# Shredmaster.net
KiCad netlist of a schematic drawn in Altium Designer
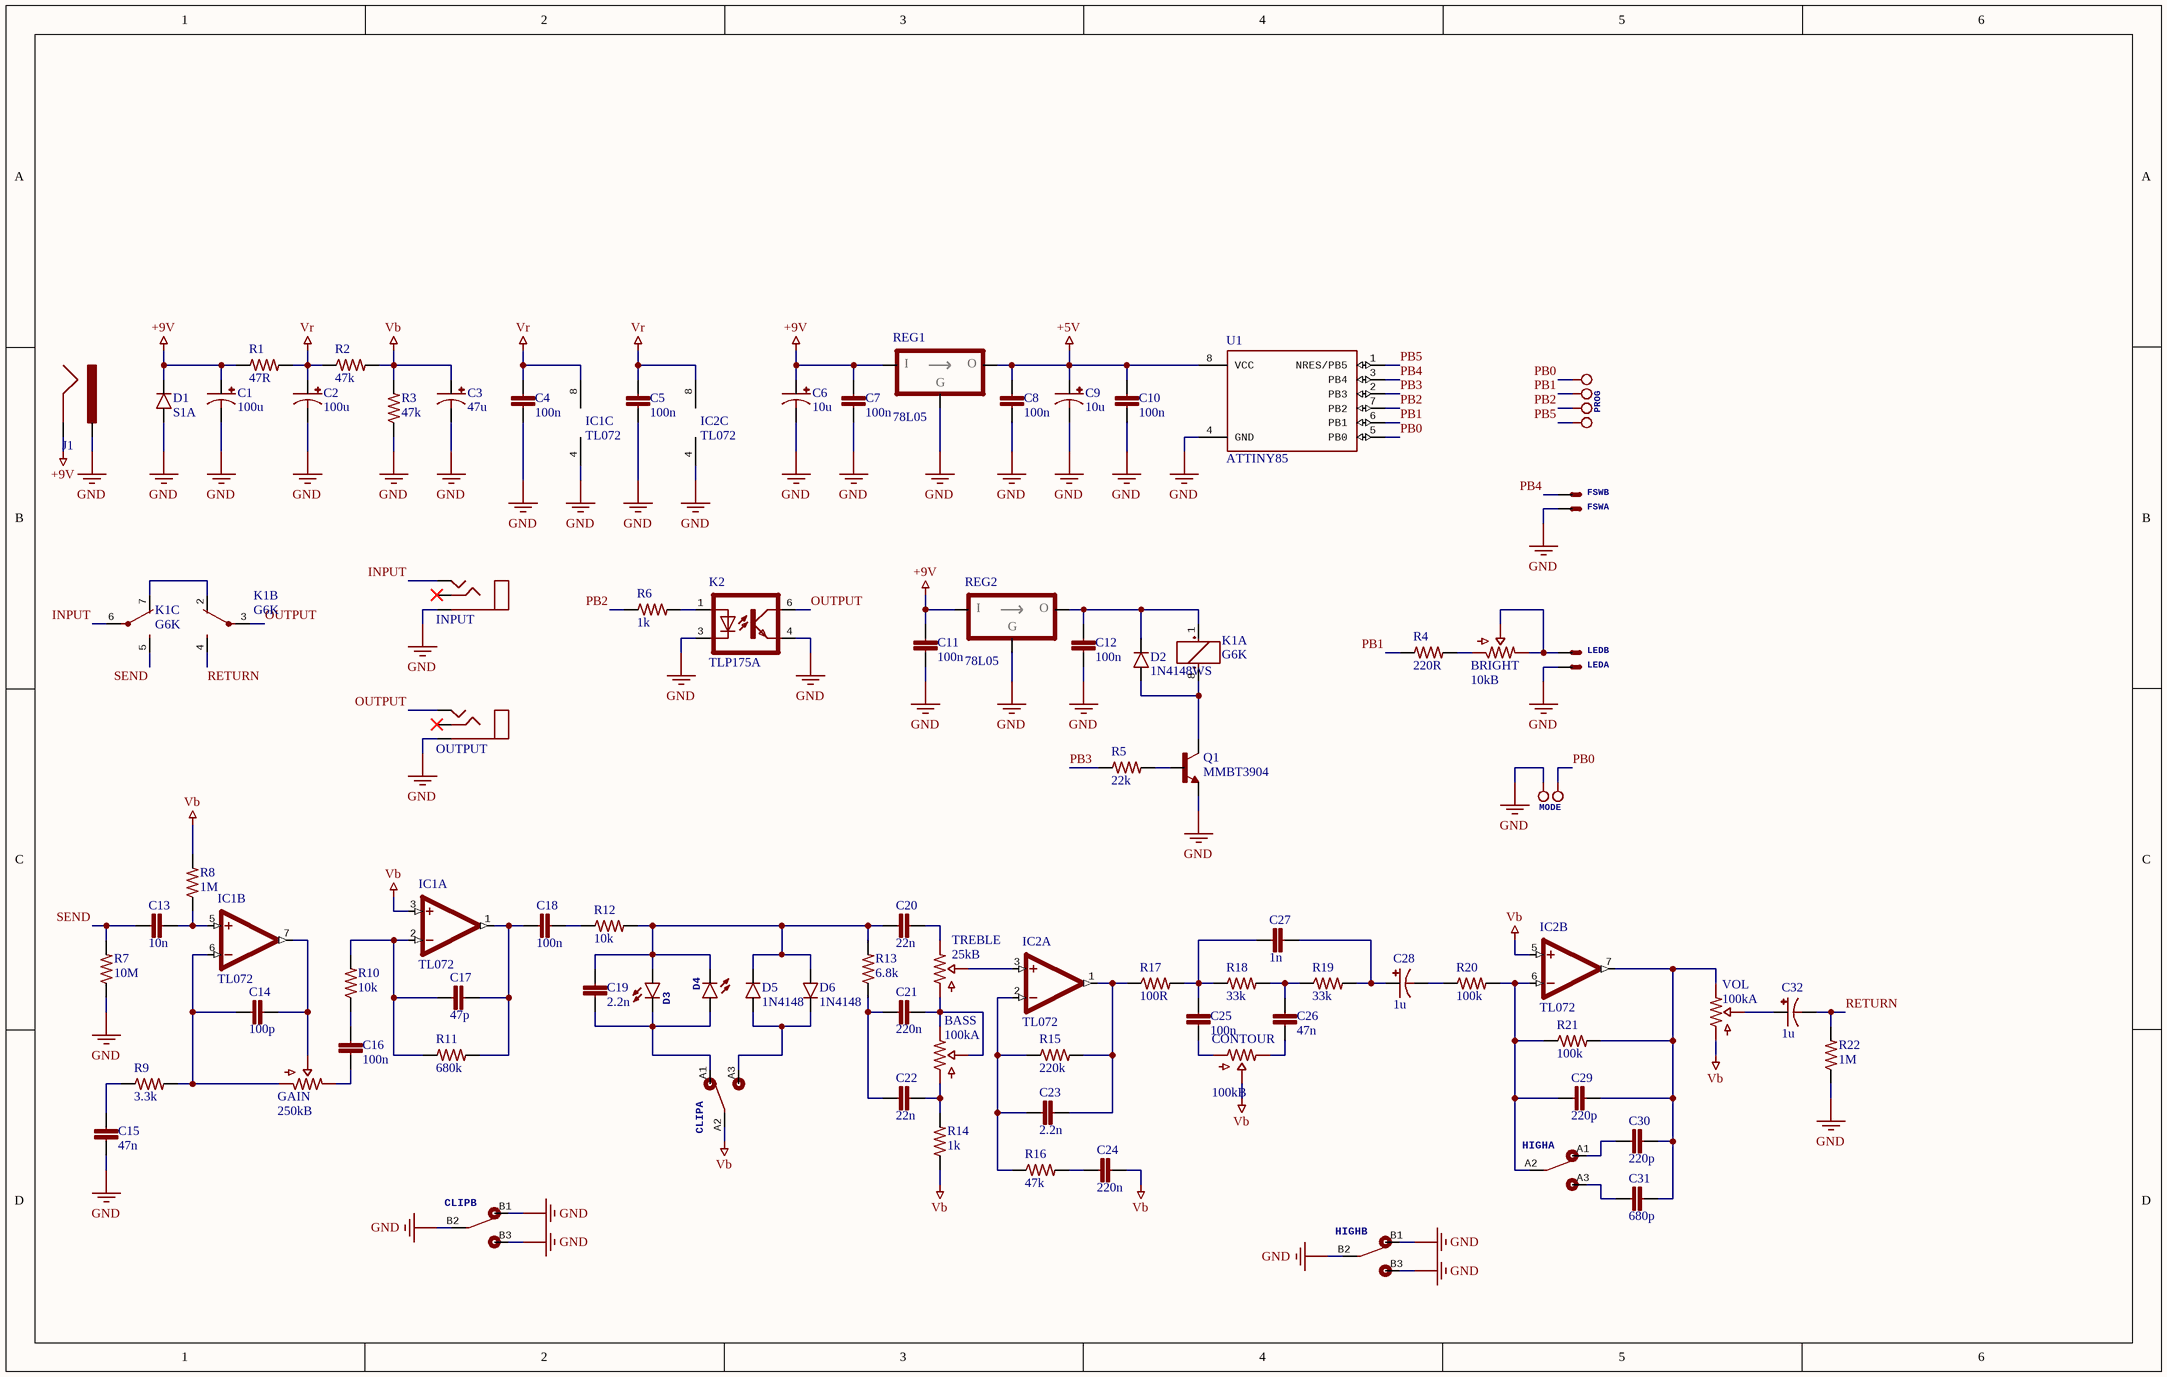
[diagram p0: Shredmaster.SchDoc]

(export (version "E")
  (design (tool "Eeschema 10.0.6"))
  (components
    (comp (ref "BASS")
      (value "100kA")
      (footprint "ALPHA_16mm_BOTTOM")
      (description "100k Log potentiometer round shaft")
      (libsource (lib "Pedals") (part "POT_100kA_ALPHA_16mm"))
    )
    (comp (ref "BRIGHT")
      (value "10kB")
      (footprint "BOURNS_3362P")
      (description "10k Lin 3362P trimmer")
      (libsource (lib "Pedals") (part "TRIM_10kB_3362P"))
    )
    (comp (ref "C1")
      (value "100u")
      (footprint "CAPAE_D")
      (description "CAP ALUM 100UF 25V SMD")
      (fields
        (field (name "MANUFACTURER") "Multicomp")
        (field (name "MANUFACTURER PART NUMBER") "MCVVT025M101EA6L")
      )
      (libsource (lib "Pedals SMD") (part "MCVVT025M101EA6L"))
    )
    (comp (ref "C2")
      (value "100u")
      (footprint "CAPAE_D")
      (description "CAP ALUM 100UF 25V SMD")
      (fields
        (field (name "MANUFACTURER") "Multicomp")
        (field (name "MANUFACTURER PART NUMBER") "MCVVT025M101EA6L")
      )
      (libsource (lib "Pedals SMD") (part "MCVVT025M101EA6L"))
    )
    (comp (ref "C3")
      (value "47u")
      (footprint "CAPAE_D")
      (description "CAP ALUM 47UF 25V SMD")
      (fields
        (field (name "MANUFACTURER") "Multicomp")
        (field (name "MANUFACTURER PART NUMBER") "MCVVT025M470EA1L")
      )
      (libsource (lib "Pedals SMD") (part "MCVVT025M470EA1L"))
    )
    (comp (ref "C4")
      (value "100n")
      (footprint "CHIP_0603")
      (description "CAP CER 100NF 50V X7R 0603")
      (fields
        (field (name "MANUFACTURER") "Multicomp")
        (field (name "MANUFACTURER PART NUMBER") "MC0603B104K500CT")
      )
      (libsource (lib "Pedals SMD") (part "MC0603B104K500CT"))
    )
    (comp (ref "C5")
      (value "100n")
      (footprint "CHIP_0603")
      (description "CAP CER 100NF 50V X7R 0603")
      (fields
        (field (name "MANUFACTURER") "Multicomp")
        (field (name "MANUFACTURER PART NUMBER") "MC0603B104K500CT")
      )
      (libsource (lib "Pedals SMD") (part "MC0603B104K500CT"))
    )
    (comp (ref "C6")
      (value "10u")
      (footprint "CAPAE_B")
      (description "CAP ALUM 10UF 25V SMD")
      (fields
        (field (name "MANUFACTURER") "Multicomp")
        (field (name "MANUFACTURER PART NUMBER") "MCVVT025M100CA1L")
      )
      (libsource (lib "Pedals SMD") (part "MCVVT025M100CA1L"))
    )
    (comp (ref "C7")
      (value "100n")
      (footprint "CHIP_0603")
      (description "CAP CER 100NF 50V X7R 0603")
      (fields
        (field (name "MANUFACTURER") "Multicomp")
        (field (name "MANUFACTURER PART NUMBER") "MC0603B104K500CT")
      )
      (libsource (lib "Pedals SMD") (part "MC0603B104K500CT"))
    )
    (comp (ref "C8")
      (value "100n")
      (footprint "CHIP_0603")
      (description "CAP CER 100NF 50V X7R 0603")
      (fields
        (field (name "MANUFACTURER") "Multicomp")
        (field (name "MANUFACTURER PART NUMBER") "MC0603B104K500CT")
      )
      (libsource (lib "Pedals SMD") (part "MC0603B104K500CT"))
    )
    (comp (ref "C9")
      (value "10u")
      (footprint "CAPAE_B")
      (description "CAP ALUM 10UF 25V SMD")
      (fields
        (field (name "MANUFACTURER") "Multicomp")
        (field (name "MANUFACTURER PART NUMBER") "MCVVT025M100CA1L")
      )
      (libsource (lib "Pedals SMD") (part "MCVVT025M100CA1L"))
    )
    (comp (ref "C10")
      (value "100n")
      (footprint "CHIP_0603")
      (description "CAP CER 100NF 50V X7R 0603")
      (fields
        (field (name "MANUFACTURER") "Multicomp")
        (field (name "MANUFACTURER PART NUMBER") "MC0603B104K500CT")
      )
      (libsource (lib "Pedals SMD") (part "MC0603B104K500CT"))
    )
    (comp (ref "C11")
      (value "100n")
      (footprint "CHIP_0603")
      (description "CAP CER 100NF 50V X7R 0603")
      (fields
        (field (name "MANUFACTURER") "Multicomp")
        (field (name "MANUFACTURER PART NUMBER") "MC0603B104K500CT")
      )
      (libsource (lib "Pedals SMD") (part "MC0603B104K500CT"))
    )
    (comp (ref "C12")
      (value "100n")
      (footprint "CHIP_0603")
      (description "CAP CER 100NF 50V X7R 0603")
      (fields
        (field (name "MANUFACTURER") "Multicomp")
        (field (name "MANUFACTURER PART NUMBER") "MC0603B104K500CT")
      )
      (libsource (lib "Pedals SMD") (part "MC0603B104K500CT"))
    )
    (comp (ref "C13")
      (value "10n")
      (footprint "CHIP_0603")
      (description "CAP CER 10NF 50V C0G/NP0 0603")
      (fields
        (field (name "MANUFACTURER") "Murata")
        (field (name "MANUFACTURER PART NUMBER") "GRM1885C1H103JA01D")
      )
      (libsource (lib "Pedals SMD") (part "GRM1885C1H103JA01D"))
    )
    (comp (ref "C14")
      (value "100p")
      (footprint "CHIP_0603")
      (description "CAP CER 100PF 50V C0G/NP0 0603")
      (fields
        (field (name "MANUFACTURER") "Multicomp")
        (field (name "MANUFACTURER PART NUMBER") "MC0603N101J500CT")
      )
      (libsource (lib "Pedals SMD") (part "MC0603N101J500CT"))
    )
    (comp (ref "C15")
      (value "47n")
      (footprint "CHIP_1206")
      (description "CAP CER 47NF 50V C0G/NP0 1206")
      (fields
        (field (name "MANUFACTURER") "Murata")
        (field (name "MANUFACTURER PART NUMBER") "GCM31M5C1H473JA16L")
      )
      (libsource (lib "Pedals SMD") (part "GCM31M5C1H473JA16L"))
    )
    (comp (ref "C16")
      (value "100n")
      (footprint "CHIP_1206")
      (description "CAP CER 100NF 50V C0G/NP0 1206")
      (fields
        (field (name "MANUFACTURER") "Murata")
        (field (name "MANUFACTURER PART NUMBER") "GRM31C5C1H104JA01L")
      )
      (libsource (lib "") (part "GRM31C5C1H104JA01L_1"))
    )
    (comp (ref "C17")
      (value "47p")
      (footprint "CHIP_0603")
      (description "CAP CER 47PF 50V C0G/NP0 0603")
      (fields
        (field (name "MANUFACTURER") "Multicomp")
        (field (name "MANUFACTURER PART NUMBER") "MC0603N470J500CT")
      )
      (libsource (lib "Pedals SMD") (part "MC0603N470J500CT"))
    )
    (comp (ref "C18")
      (value "100n")
      (footprint "CHIP_1206")
      (description "CAP CER 100NF 50V C0G/NP0 1206")
      (fields
        (field (name "MANUFACTURER") "Murata")
        (field (name "MANUFACTURER PART NUMBER") "GRM31C5C1H104JA01L")
      )
      (libsource (lib "Pedals SMD") (part "GRM31C5C1H104JA01L"))
    )
    (comp (ref "C19")
      (value "2.2n")
      (footprint "CHIP_0603")
      (description "CAP CER 2.2NF 50V C0G/NP0 0603")
      (fields
        (field (name "MANUFACTURER") "Murata")
        (field (name "MANUFACTURER PART NUMBER") "GRM1885C1H222JA01D")
      )
      (libsource (lib "") (part "GRM1885C1H222JA01D_1"))
    )
    (comp (ref "C20")
      (value "22n")
      (footprint "CHIP_0805")
      (description "CAP CER 22NF 50V C0G/NP0 0805")
      (fields
        (field (name "MANUFACTURER") "Murata")
        (field (name "MANUFACTURER PART NUMBER") "GRM21B5C1H223JA01L")
      )
      (libsource (lib "Pedals SMD") (part "GRM21B5C1H223JA01L"))
    )
    (comp (ref "C21")
      (value "220n")
      (footprint "CHIP_0603")
      (description "CAP CER 220n 50V X7R 0603")
      (fields
        (field (name "MANUFACTURER") "Murata")
        (field (name "MANUFACTURER PART NUMBER") "GCM188R71H224KA64D")
      )
      (libsource (lib "Pedals SMD") (part "GCM188R71H224KA64D"))
    )
    (comp (ref "C22")
      (value "22n")
      (footprint "CHIP_0805")
      (description "CAP CER 22NF 50V C0G/NP0 0805")
      (fields
        (field (name "MANUFACTURER") "Murata")
        (field (name "MANUFACTURER PART NUMBER") "GRM21B5C1H223JA01L")
      )
      (libsource (lib "Pedals SMD") (part "GRM21B5C1H223JA01L"))
    )
    (comp (ref "C23")
      (value "2.2n")
      (footprint "CHIP_0603")
      (description "CAP CER 2.2NF 50V C0G/NP0 0603")
      (fields
        (field (name "MANUFACTURER") "Murata")
        (field (name "MANUFACTURER PART NUMBER") "GRM1885C1H222JA01D")
      )
      (libsource (lib "Pedals SMD") (part "GRM1885C1H222JA01D"))
    )
    (comp (ref "C24")
      (value "220n")
      (footprint "CHIP_0603")
      (description "CAP CER 220n 50V X7R 0603")
      (fields
        (field (name "MANUFACTURER") "Murata")
        (field (name "MANUFACTURER PART NUMBER") "GCM188R71H224KA64D")
      )
      (libsource (lib "Pedals SMD") (part "GCM188R71H224KA64D"))
    )
    (comp (ref "C25")
      (value "100n")
      (footprint "CHIP_1206")
      (description "CAP CER 100NF 50V C0G/NP0 1206")
      (fields
        (field (name "MANUFACTURER") "Murata")
        (field (name "MANUFACTURER PART NUMBER") "GRM31C5C1H104JA01L")
      )
      (libsource (lib "") (part "GRM31C5C1H104JA01L_1"))
    )
    (comp (ref "C26")
      (value "47n")
      (footprint "CHIP_1206")
      (description "CAP CER 47NF 50V C0G/NP0 1206")
      (fields
        (field (name "MANUFACTURER") "Murata")
        (field (name "MANUFACTURER PART NUMBER") "GCM31M5C1H473JA16L")
      )
      (libsource (lib "Pedals SMD") (part "GCM31M5C1H473JA16L"))
    )
    (comp (ref "C27")
      (value "1n")
      (footprint "CHIP_0603")
      (description "CAP CER 1NF 50V C0G/NP0 0603")
      (fields
        (field (name "MANUFACTURER") "Murata")
        (field (name "MANUFACTURER PART NUMBER") "GRM1885C1H102JA01D")
      )
      (libsource (lib "Pedals SMD") (part "GRM1885C1H102JA01D"))
    )
    (comp (ref "C28")
      (value "1u")
      (footprint "CAPAE_B")
      (description "CAP ALUM 1UF 50V LESR SMD")
      (fields
        (field (name "MANUFACTURER") "Panasonic")
        (field (name "MANUFACTURER PART NUMBER") "EEEFC1H1R0R")
      )
      (libsource (lib "Pedals SMD") (part "EEEFC1H1R0R"))
    )
    (comp (ref "C29")
      (value "220p")
      (footprint "CHIP_0603")
      (description "CAP CER 220PF 50V C0G/NP0 0603")
      (fields
        (field (name "MANUFACTURER") "Multicomp")
        (field (name "MANUFACTURER PART NUMBER") "MC0603N221J500CT")
      )
      (libsource (lib "Pedals SMD") (part "MC0603N221J500CT"))
    )
    (comp (ref "C30")
      (value "220p")
      (footprint "CHIP_0603")
      (description "CAP CER 220PF 50V C0G/NP0 0603")
      (fields
        (field (name "MANUFACTURER") "Multicomp")
        (field (name "MANUFACTURER PART NUMBER") "MC0603N221J500CT")
      )
      (libsource (lib "Pedals SMD") (part "MC0603N221J500CT"))
    )
    (comp (ref "C31")
      (value "680p")
      (footprint "CHIP_0603")
      (description "CAP CER 680PF 50V C0G/NP0 0603")
      (fields
        (field (name "MANUFACTURER") "Multicomp")
        (field (name "MANUFACTURER PART NUMBER") "MC0603N681J500CT")
      )
      (libsource (lib "Pedals SMD") (part "MC0603N681J500CT"))
    )
    (comp (ref "C32")
      (value "1u")
      (footprint "CAPAE_B")
      (description "CAP ALUM 1UF 50V LESR SMD")
      (fields
        (field (name "MANUFACTURER") "Panasonic")
        (field (name "MANUFACTURER PART NUMBER") "EEEFC1H1R0R")
      )
      (libsource (lib "Pedals SMD") (part "EEEFC1H1R0R"))
    )
    (comp (ref "CLIP")
      (value "DPDT")
      (footprint "DPDT_SLIDE")
      (description "DPDT slide switch ON/OFF/ON")
      (libsource (lib "") (part "SW_SLIDE_DPDT_ON-OFF-ON_2"))
    )
    (comp (ref "CONTOUR")
      (value "100kB")
      (footprint "ALPHA_16mm_BOTTOM")
      (description "100k Lin potentiometer round shaft")
      (libsource (lib "Pedals") (part "POT_100kB_ALPHA_16mm"))
    )
    (comp (ref "D1")
      (value "S1A")
      (footprint "DO214")
      (description "DIODE GEN PURP 50V 1A SMA")
      (fields (field (name "MANUFACTURER") "ON Semiconductor / Fairchild"))
      (libsource (lib "Pedals SMD") (part "S1A"))
    )
    (comp (ref "D2")
      (value "1N4148WS")
      (footprint "SOD323")
      (description "DIODE GEN PURP 75V 150MA SOD323F")
      (fields (field (name "MANUFACTURER") "ON Semiconductor / Fairchild"))
      (libsource (lib "Pedals SMD") (part "1N4148WS"))
    )
    (comp (ref "D3")
      (value "D_LED")
      (footprint "LED_3MM")
      (description "LED")
      (libsource (lib "Pedals") (part "D_LED"))
    )
    (comp (ref "D4")
      (value "D_LED")
      (footprint "LED_3MM")
      (description "LED")
      (libsource (lib "Pedals") (part "D_LED"))
    )
    (comp (ref "D5") (value "1N4148") (footprint "DO35_2") (libsource (lib "Pedals") (part "D_1N4148")))
    (comp (ref "D6") (value "1N4148") (footprint "DO35_2") (libsource (lib "Pedals") (part "D_1N4148")))
    (comp (ref "FSW")
      (value "J_JST-XH-02")
      (footprint "JST-XH-02")
      (description "2 Pins male XH header")
      (libsource (lib "Pedals") (part "J_JST-XH-02"))
    )
    (comp (ref "GAIN")
      (value "250kB")
      (footprint "ALPHA_16mm_BOTTOM")
      (description "250k Lin potentiometer round shaft")
      (libsource (lib "Pedals") (part "POT_250kB_ALPHA_16mm"))
    )
    (comp (ref "HIGH")
      (value "DPDT")
      (footprint "DPDT_SLIDE")
      (description "DPDT slide switch ON/OFF/ON")
      (libsource (lib "Pedals") (part "SW_SLIDE_DPDT_ON-OFF-ON"))
    )
    (comp (ref "IC1")
      (value "TL072")
      (footprint "SO-8")
      (description "IC OPAMP JFET 4MHZ 8SO")
      (fields
        (field (name "MANUFACTURER") "STMicroelectronics")
        (field (name "MANUFACTURER PART NUMBER") "TL072CDT")
      )
      (libsource (lib "Pedals SMD") (part "TL072CDT"))
    )
    (comp (ref "IC2")
      (value "TL072")
      (footprint "SO-8")
      (description "IC OPAMP JFET 4MHZ 8SO")
      (fields
        (field (name "MANUFACTURER") "STMicroelectronics")
        (field (name "MANUFACTURER PART NUMBER") "TL072CDT")
      )
      (libsource (lib "Pedals SMD") (part "TL072CDT"))
    )
    (comp (ref "INPUT")
      (value "J_STEREO")
      (footprint "STEREO")
      (description "6.35mm stereo insulated socket jack PCB mounted")
      (libsource (lib "Pedals") (part "J_STEREO"))
    )
    (comp (ref "J1")
      (value "J_DC_JACK")
      (footprint "DC_JACK")
      (description "DC Power jack 2.1mm barrel")
      (libsource (lib "Pedals") (part "J_DC_JACK"))
    )
    (comp (ref "K1")
      (value "G6K")
      (footprint "G6K")
      (description "OMRON - G6K-2F 5DC - RELAY, SIGNAL, DPDT, 30VDC, 1A")
      (fields (field (name "MANUFACTURER") "Cliff") (field (name "MANUFACTURER PART NUMBER") "G6K-2F5DC"))
      (libsource (lib "Pedals SMD") (part "G6K-2F5DC"))
    )
    (comp (ref "K2")
      (value "TLP175A")
      (footprint "TLP175A")
      (description "Toshiba TLP175A AC Input MOSFET Output Optocoupler, Surface Mount, 4-Pin SOIC")
      (fields (field (name "MANUFACTURER") "Toshiba"))
      (libsource (lib "Pedals SMD") (part "TLP175A"))
    )
    (comp (ref "LED")
      (value "J_JST-XH-02")
      (footprint "JST-XH-02")
      (description "2 Pins male XH header")
      (libsource (lib "Pedals") (part "J_JST-XH-02"))
    )
    (comp (ref "MODE")
      (value "J_HEADER_2PINS")
      (footprint "HEADER_2PINS")
      (description "2 Pins male header")
      (libsource (lib "Pedals") (part "J_HEADER_2PINS"))
    )
    (comp (ref "OUTPUT")
      (value "J_STEREO")
      (footprint "STEREO")
      (description "6.35mm stereo insulated socket jack PCB mounted")
      (libsource (lib "Pedals") (part "J_STEREO"))
    )
    (comp (ref "PROG")
      (value "J_HEADER_4PINS_FEM")
      (footprint "HEADER_4Pins_FEM")
      (description "4 Pins female header")
      (libsource (lib "Pedals") (part "J_HEADER_4PINS_FEM"))
    )
    (comp (ref "Q1")
      (value "MMBT3904")
      (footprint "SOT23")
      (description "TRANS NPN 40V 0.2A SOT23")
      (fields
        (field (name "MANUFACTURER") "ON Semiconductor")
        (field (name "MANUFACTURER PART NUMBER") "MMBT3904LT1G")
      )
      (libsource (lib "Pedals SMD") (part "MMBT3904LT1G"))
    )
    (comp (ref "R1")
      (value "47R")
      (footprint "CHIP_R_1206")
      (description "RES SMD 47 OHM 1% 1/4W 1206")
      (fields
        (field (name "MANUFACTURER") "Vishay")
        (field (name "MANUFACTURER PART NUMBER") "CRCW120647R0FKEA")
      )
      (libsource (lib "Pedals SMD") (part "CRCW120647R0FKEA"))
    )
    (comp (ref "R2")
      (value "47k")
      (footprint "CHIP_R_1206")
      (description "RES SMD 47K OHM 1% 1/4W 1206")
      (fields
        (field (name "MANUFACTURER") "Vishay")
        (field (name "MANUFACTURER PART NUMBER") "CRCW120647K0FKEA")
      )
      (libsource (lib "Pedals SMD") (part "CRCW120647K0FKEA"))
    )
    (comp (ref "R3")
      (value "47k")
      (footprint "CHIP_R_1206")
      (description "RES SMD 47K OHM 1% 1/4W 1206")
      (fields
        (field (name "MANUFACTURER") "Vishay")
        (field (name "MANUFACTURER PART NUMBER") "CRCW120647K0FKEA")
      )
      (libsource (lib "Pedals SMD") (part "CRCW120647K0FKEA"))
    )
    (comp (ref "R4")
      (value "220R")
      (footprint "CHIP_R_1206")
      (description "RES SMD 220 OHM 1% 1/4W 1206")
      (fields
        (field (name "MANUFACTURER") "Vishay")
        (field (name "MANUFACTURER PART NUMBER") "CRCW1206220RFKEA")
      )
      (libsource (lib "Pedals SMD") (part "CRCW1206220RFKEA"))
    )
    (comp (ref "R5")
      (value "22k")
      (footprint "CHIP_R_0603")
      (description "RES SMD 22K OHM 1% 1/10W 0603")
      (fields
        (field (name "MANUFACTURER") "Vishay")
        (field (name "MANUFACTURER PART NUMBER") "CRCW060322K0FKEA")
      )
      (libsource (lib "Pedals SMD") (part "CRCW060322K0FKEA"))
    )
    (comp (ref "R6")
      (value "1k")
      (footprint "CHIP_R_0603")
      (description "RES SMD 1K OHM 1% 1/10W 0603")
      (fields
        (field (name "MANUFACTURER") "Vishay Dale")
        (field (name "MANUFACTURER PART NUMBER") "CRCW06031K00FKEA")
      )
      (libsource (lib "Pedals SMD") (part "CRCW06031K00FKEA"))
    )
    (comp (ref "R7")
      (value "10M")
      (footprint "CHIP_R_0603")
      (description "RES SMD 10M OHM 1% 1/10W 0603")
      (fields
        (field (name "MANUFACTURER") "Vishay")
        (field (name "MANUFACTURER PART NUMBER") "CRCW060310M0FKEA")
      )
      (libsource (lib "Pedals SMD") (part "CRCW060310M0FKEA"))
    )
    (comp (ref "R8")
      (value "1M")
      (footprint "CHIP_R_0603")
      (description "RES SMD 1M OHM 1% 1/10W 0603")
      (fields
        (field (name "MANUFACTURER") "Vishay")
        (field (name "MANUFACTURER PART NUMBER") "CRCW06031M00FKEA")
      )
      (libsource (lib "Pedals SMD") (part "CRCW06031M00FKEA"))
    )
    (comp (ref "R9")
      (value "3.3k")
      (footprint "CHIP_R_0603")
      (description "RES SMD 3.3K OHM 1% 1/10W 0603")
      (fields
        (field (name "MANUFACTURER") "Vishay")
        (field (name "MANUFACTURER PART NUMBER") "CRCW06033K30FKEA")
      )
      (libsource (lib "Pedals SMD") (part "CRCW06033K30FKEA"))
    )
    (comp (ref "R10")
      (value "10k")
      (footprint "CHIP_R_0603")
      (description "RES SMD 10K OHM 1% 1/10W 0603")
      (fields
        (field (name "MANUFACTURER") "Vishay")
        (field (name "MANUFACTURER PART NUMBER") "CRCW060310K0FKEA")
      )
      (libsource (lib "Pedals SMD") (part "CRCW060310K0FKEA"))
    )
    (comp (ref "R11")
      (value "680k")
      (footprint "CHIP_R_0603")
      (description "RES SMD 680K OHM 1% 1/10W 0603")
      (fields
        (field (name "MANUFACTURER") "Vishay")
        (field (name "MANUFACTURER PART NUMBER") "CRCW0603680KFKEA")
      )
      (libsource (lib "Pedals SMD") (part "CRCW0603680KFKEA"))
    )
    (comp (ref "R12")
      (value "10k")
      (footprint "CHIP_R_0603")
      (description "RES SMD 10K OHM 1% 1/10W 0603")
      (fields
        (field (name "MANUFACTURER") "Vishay")
        (field (name "MANUFACTURER PART NUMBER") "CRCW060310K0FKEA")
      )
      (libsource (lib "Pedals SMD") (part "CRCW060310K0FKEA"))
    )
    (comp (ref "R13")
      (value "6.8k")
      (footprint "CHIP_R_0603")
      (description "RES SMD 6.8K OHM 1% 1/10W 0603")
      (fields
        (field (name "MANUFACTURER") "Vishay")
        (field (name "MANUFACTURER PART NUMBER") "CRCW06036K80FKEA")
      )
      (libsource (lib "Pedals SMD") (part "CRCW06036K80FKEA"))
    )
    (comp (ref "R14")
      (value "1k")
      (footprint "CHIP_R_0603")
      (description "RES SMD 1K OHM 1% 1/10W 0603")
      (fields
        (field (name "MANUFACTURER") "Vishay Dale")
        (field (name "MANUFACTURER PART NUMBER") "CRCW06031K00FKEA")
      )
      (libsource (lib "Pedals SMD") (part "CRCW06031K00FKEA"))
    )
    (comp (ref "R15")
      (value "220k")
      (footprint "CHIP_R_0603")
      (description "RES SMD 220K OHM 1% 1/10W 0603")
      (fields
        (field (name "MANUFACTURER") "Vishay")
        (field (name "MANUFACTURER PART NUMBER") "CRCW0603220KFKEA")
      )
      (libsource (lib "Pedals SMD") (part "CRCW0603220KFKEA"))
    )
    (comp (ref "R16")
      (value "47k")
      (footprint "CHIP_R_0603")
      (description "RES SMD 47K OHM 1% 1/10W 0603")
      (fields
        (field (name "MANUFACTURER") "Vishay")
        (field (name "MANUFACTURER PART NUMBER") "CRCW060347K0FKEA")
      )
      (libsource (lib "Pedals SMD") (part "CRCW060347K0FKEA"))
    )
    (comp (ref "R17")
      (value "100R")
      (footprint "CHIP_R_0603")
      (description "RES SMD 100 OHM 1% 1/10W 0603")
      (fields
        (field (name "MANUFACTURER") "Vishay Dale")
        (field (name "MANUFACTURER PART NUMBER") "CRCW0603100RFKEA")
      )
      (libsource (lib "Pedals SMD") (part "CRCW0603100RFKEA"))
    )
    (comp (ref "R18")
      (value "33k")
      (footprint "CHIP_R_0603")
      (description "RES SMD 33K OHM 1% 1/10W 0603")
      (fields
        (field (name "MANUFACTURER") "Vishay")
        (field (name "MANUFACTURER PART NUMBER") "CRCW060333K0FKEA")
      )
      (libsource (lib "Pedals SMD") (part "CRCW060333K0FKEA"))
    )
    (comp (ref "R19")
      (value "33k")
      (footprint "CHIP_R_0603")
      (description "RES SMD 33K OHM 1% 1/10W 0603")
      (fields
        (field (name "MANUFACTURER") "Vishay")
        (field (name "MANUFACTURER PART NUMBER") "CRCW060333K0FKEA")
      )
      (libsource (lib "Pedals SMD") (part "CRCW060333K0FKEA"))
    )
    (comp (ref "R20")
      (value "100k")
      (footprint "CHIP_R_0603")
      (description "RES SMD 100K OHM 1% 1/10W 0603")
      (fields
        (field (name "MANUFACTURER") "Vishay")
        (field (name "MANUFACTURER PART NUMBER") "CRCW0603100KFKEA")
      )
      (libsource (lib "Pedals SMD") (part "CRCW0603100KFKEA"))
    )
    (comp (ref "R21")
      (value "100k")
      (footprint "CHIP_R_0603")
      (description "RES SMD 100K OHM 1% 1/10W 0603")
      (fields
        (field (name "MANUFACTURER") "Vishay")
        (field (name "MANUFACTURER PART NUMBER") "CRCW0603100KFKEA")
      )
      (libsource (lib "Pedals SMD") (part "CRCW0603100KFKEA"))
    )
    (comp (ref "R22")
      (value "1M")
      (footprint "CHIP_R_0603")
      (description "RES SMD 1M OHM 1% 1/10W 0603")
      (fields
        (field (name "MANUFACTURER") "Vishay")
        (field (name "MANUFACTURER PART NUMBER") "CRCW06031M00FKEA")
      )
      (libsource (lib "Pedals SMD") (part "CRCW06031M00FKEA"))
    )
    (comp (ref "REG1")
      (value "78L05")
      (footprint "SOT23-3")
      (description "TAIWAN SEMICONDUCTOR - TS78L05CX RFG - REG 3-TERMINAL 100MA, SMD, SOT23-3")
      (fields
        (field (name "MANUFACTURER") "Taiwan Semiconductor")
        (field (name "MANUFACTURER PART NUMBER") "TS78L05CXRFG")
      )
      (libsource (lib "Pedals SMD") (part "TS78L05CXRFG"))
    )
    (comp (ref "REG2")
      (value "78L05")
      (footprint "SOT23-3")
      (description "TAIWAN SEMICONDUCTOR - TS78L05CX RFG - REG 3-TERMINAL 100MA, SMD, SOT23-3")
      (fields
        (field (name "MANUFACTURER") "Taiwan Semiconductor")
        (field (name "MANUFACTURER PART NUMBER") "TS78L05CXRFG")
      )
      (libsource (lib "Pedals SMD") (part "TS78L05CXRFG"))
    )
    (comp (ref "TREBLE")
      (value "25kB")
      (footprint "ALPHA_16mm_BOTTOM")
      (description "25k Lin potentiometer round shaft")
      (libsource (lib "Pedals") (part "POT_25kB_ALPHA_16mm"))
    )
    (comp (ref "U1")
      (value "ATTINY85")
      (footprint "SOP8")
      (description "IC, 8BIT MCU, AVR TINY, 20MHZ, 8-SOIC")
      (fields
        (field (name "MANUFACTURER") "Microchip / Atmel")
        (field (name "MANUFACTURER PART NUMBER") "ATTINY85-20SU")
      )
      (libsource (lib "Pedals SMD") (part "ATTINY85-20SU"))
    )
    (comp (ref "VOL")
      (value "100kA")
      (footprint "ALPHA_16mm_BOTTOM")
      (description "100k Log potentiometer round shaft")
      (libsource (lib "Pedals") (part "POT_100kA_ALPHA_16mm"))
    )
  )
  (nets
    (net (code "1") (name "+5V") (class "Default")
      (node (ref "C10") (pin "1") (pinfunction "1_1") (pintype "passive"))
      (node (ref "C8") (pin "1") (pinfunction "1_1") (pintype "passive"))
      (node (ref "C9") (pin "+") (pinfunction "+_+") (pintype "passive"))
      (node (ref "REG1") (pin "1") (pinfunction "OUTPUT_1") (pintype "power_in"))
      (node (ref "U1") (pin "8") (pinfunction "VCC_8") (pintype "power_in"))
    )
    (net (code "2") (name "+9V") (class "Default")
      (node (ref "C1") (pin "+") (pinfunction "+_+") (pintype "passive"))
      (node (ref "C11") (pin "1") (pinfunction "1_1") (pintype "passive"))
      (node (ref "C6") (pin "+") (pinfunction "+_+") (pintype "passive"))
      (node (ref "C7") (pin "1") (pinfunction "1_1") (pintype "passive"))
      (node (ref "D1") (pin "1") (pinfunction "1_1") (pintype "passive"))
      (node (ref "J1") (pin "GND") (pinfunction "GND_GND") (pintype "passive"))
      (node (ref "R1") (pin "1") (pinfunction "1_1") (pintype "passive"))
      (node (ref "REG1") (pin "2") (pinfunction "INPUT_2") (pintype "power_in"))
      (node (ref "REG2") (pin "2") (pinfunction "INPUT_2") (pintype "power_in"))
    )
    (net (code "3") (name "/INPUT") (class "Default")
      (node (ref "INPUT") (pin "T") (pinfunction "T_T") (pintype "passive"))
      (node (ref "K1") (pin "6") (pinfunction "P_6") (pintype "passive"))
    )
    (net (code "4") (name "/OUTPUT") (class "Default")
      (node (ref "K1") (pin "3") (pinfunction "P_3") (pintype "passive"))
      (node (ref "K2") (pin "6") (pinfunction "COL_6") (pintype "passive"))
      (node (ref "OUTPUT") (pin "T") (pinfunction "T_T") (pintype "passive"))
    )
    (net (code "5") (name "/PB0") (class "Default")
      (node (ref "MODE") (pin "2") (pinfunction "2_2") (pintype "passive"))
      (node (ref "PROG") (pin "4") (pinfunction "4_4") (pintype "passive"))
      (node (ref "U1") (pin "5") (pinfunction "PB0_5") (pintype "bidirectional"))
    )
    (net (code "6") (name "/PB1") (class "Default")
      (node (ref "PROG") (pin "3") (pinfunction "3_3") (pintype "passive"))
      (node (ref "R4") (pin "1") (pinfunction "1_1") (pintype "passive"))
      (node (ref "U1") (pin "6") (pinfunction "PB1_6") (pintype "bidirectional"))
    )
    (net (code "7") (name "/PB2") (class "Default")
      (node (ref "PROG") (pin "2") (pinfunction "2_2") (pintype "passive"))
      (node (ref "R6") (pin "1") (pinfunction "1_1") (pintype "passive"))
      (node (ref "U1") (pin "7") (pinfunction "PB2_7") (pintype "bidirectional"))
    )
    (net (code "8") (name "/PB3") (class "Default")
      (node (ref "R5") (pin "1") (pinfunction "1_1") (pintype "passive"))
      (node (ref "U1") (pin "2") (pinfunction "PB3_2") (pintype "bidirectional"))
    )
    (net (code "9") (name "/PB4") (class "Default")
      (node (ref "FSW") (pin "1") (pinfunction "S_1") (pintype "passive"))
      (node (ref "U1") (pin "3") (pinfunction "PB4_3") (pintype "bidirectional"))
    )
    (net (code "10") (name "/PB5") (class "Default")
      (node (ref "PROG") (pin "1") (pinfunction "1_1") (pintype "passive"))
      (node (ref "U1") (pin "1") (pinfunction "NRES/PB5_1") (pintype "bidirectional"))
    )
    (net (code "11") (name "/RETURN") (class "Default")
      (node (ref "C32") (pin "-") (pinfunction "-_-") (pintype "passive"))
      (node (ref "K1") (pin "4") (pinfunction "S_4") (pintype "passive"))
      (node (ref "R22") (pin "2") (pinfunction "2_2") (pintype "passive"))
    )
    (net (code "12") (name "/SEND") (class "Default")
      (node (ref "C13") (pin "2") (pinfunction "2_2") (pintype "passive"))
      (node (ref "K1") (pin "5") (pinfunction "S_5") (pintype "passive"))
      (node (ref "R7") (pin "2") (pinfunction "2_2") (pintype "passive"))
    )
    (net (code "13") (name "GND") (class "Default")
      (node (ref "C1") (pin "-") (pinfunction "-_-") (pintype "passive"))
      (node (ref "C10") (pin "2") (pinfunction "2_2") (pintype "passive"))
      (node (ref "C11") (pin "2") (pinfunction "2_2") (pintype "passive"))
      (node (ref "C12") (pin "2") (pinfunction "2_2") (pintype "passive"))
      (node (ref "C15") (pin "2") (pinfunction "2_2") (pintype "passive"))
      (node (ref "C2") (pin "-") (pinfunction "-_-") (pintype "passive"))
      (node (ref "C3") (pin "-") (pinfunction "-_-") (pintype "passive"))
      (node (ref "C4") (pin "2") (pinfunction "2_2") (pintype "passive"))
      (node (ref "C5") (pin "2") (pinfunction "2_2") (pintype "passive"))
      (node (ref "C6") (pin "-") (pinfunction "-_-") (pintype "passive"))
      (node (ref "C7") (pin "2") (pinfunction "2_2") (pintype "passive"))
      (node (ref "C8") (pin "2") (pinfunction "2_2") (pintype "passive"))
      (node (ref "C9") (pin "-") (pinfunction "-_-") (pintype "passive"))
      (node (ref "CLIP") (pin "B1") (pinfunction "1_B1") (pintype "passive"))
      (node (ref "CLIP") (pin "B2") (pinfunction "2_B2") (pintype "passive"))
      (node (ref "CLIP") (pin "B3") (pinfunction "3_B3") (pintype "passive"))
      (node (ref "D1") (pin "2") (pinfunction "2_2") (pintype "passive"))
      (node (ref "FSW") (pin "2") (pinfunction "S_2") (pintype "passive"))
      (node (ref "HIGH") (pin "B1") (pinfunction "1_B1") (pintype "passive"))
      (node (ref "HIGH") (pin "B2") (pinfunction "2_B2") (pintype "passive"))
      (node (ref "HIGH") (pin "B3") (pinfunction "3_B3") (pintype "passive"))
      (node (ref "IC1") (pin "4") (pinfunction "V-_4") (pintype "power_in"))
      (node (ref "IC2") (pin "4") (pinfunction "V-_4") (pintype "power_in"))
      (node (ref "INPUT") (pin "S") (pinfunction "S_S") (pintype "passive"))
      (node (ref "J1") (pin "PWR") (pinfunction "PWR_PWR") (pintype "passive"))
      (node (ref "K2") (pin "3") (pinfunction "C_3") (pintype "passive"))
      (node (ref "K2") (pin "4") (pinfunction "EMIT_4") (pintype "passive"))
      (node (ref "LED") (pin "2") (pinfunction "S_2") (pintype "passive"))
      (node (ref "MODE") (pin "1") (pinfunction "1_1") (pintype "passive"))
      (node (ref "OUTPUT") (pin "S") (pinfunction "S_S") (pintype "passive"))
      (node (ref "Q1") (pin "2") (pinfunction "E_2") (pintype "passive"))
      (node (ref "R22") (pin "1") (pinfunction "1_1") (pintype "passive"))
      (node (ref "R3") (pin "1") (pinfunction "1_1") (pintype "passive"))
      (node (ref "R7") (pin "1") (pinfunction "1_1") (pintype "passive"))
      (node (ref "REG1") (pin "3") (pinfunction "COMMON_3") (pintype "power_in"))
      (node (ref "REG2") (pin "3") (pinfunction "COMMON_3") (pintype "power_in"))
      (node (ref "U1") (pin "4") (pinfunction "GND_4") (pintype "power_in"))
    )
    (net (code "14") (name "Net-(BASS-Pad1)") (class "Default")
      (node (ref "BASS") (pin "1") (pinfunction "1_1") (pintype "passive"))
      (node (ref "C22") (pin "1") (pinfunction "1_1") (pintype "passive"))
      (node (ref "R14") (pin "2") (pinfunction "2_2") (pintype "passive"))
    )
    (net (code "15") (name "Net-(BASS-Pad2)") (class "Default")
      (node (ref "BASS") (pin "2") (pinfunction "2_2") (pintype "passive"))
      (node (ref "BASS") (pin "3") (pinfunction "3_3") (pintype "passive"))
      (node (ref "C21") (pin "1") (pinfunction "1_1") (pintype "passive"))
      (node (ref "TREBLE") (pin "1") (pinfunction "1_1") (pintype "passive"))
    )
    (net (code "16") (name "Net-(BRIGHT-Pad1)") (class "Default")
      (node (ref "BRIGHT") (pin "1") (pinfunction "1_1") (pintype "passive"))
      (node (ref "R4") (pin "2") (pinfunction "2_2") (pintype "passive"))
    )
    (net (code "17") (name "Net-(C15-Pad1)") (class "Default")
      (node (ref "C15") (pin "1") (pinfunction "1_1") (pintype "passive"))
      (node (ref "R9") (pin "1") (pinfunction "1_1") (pintype "passive"))
    )
    (net (code "18") (name "Net-(C16-Pad1)") (class "Default")
      (node (ref "C16") (pin "1") (pinfunction "1_1") (pintype "passive"))
      (node (ref "R10") (pin "1") (pinfunction "1_1") (pintype "passive"))
    )
    (net (code "19") (name "Net-(C16-Pad2)") (class "Default")
      (node (ref "C16") (pin "2") (pinfunction "2_2") (pintype "passive"))
      (node (ref "GAIN") (pin "3") (pinfunction "3_3") (pintype "passive"))
    )
    (net (code "20") (name "Net-(C18-Pad1)") (class "Default")
      (node (ref "C18") (pin "1") (pinfunction "1_1") (pintype "passive"))
      (node (ref "R12") (pin "1") (pinfunction "1_1") (pintype "passive"))
    )
    (net (code "21") (name "Net-(C20-Pad1)") (class "Default")
      (node (ref "C20") (pin "1") (pinfunction "1_1") (pintype "passive"))
      (node (ref "TREBLE") (pin "3") (pinfunction "3_3") (pintype "passive"))
    )
    (net (code "22") (name "Net-(C21-Pad2)") (class "Default")
      (node (ref "C21") (pin "2") (pinfunction "2_2") (pintype "passive"))
      (node (ref "C22") (pin "2") (pinfunction "2_2") (pintype "passive"))
      (node (ref "R13") (pin "1") (pinfunction "1_1") (pintype "passive"))
    )
    (net (code "23") (name "Net-(C24-Pad2)") (class "Default")
      (node (ref "C24") (pin "2") (pinfunction "2_2") (pintype "passive"))
      (node (ref "R16") (pin "2") (pinfunction "2_2") (pintype "passive"))
    )
    (net (code "24") (name "Net-(C25-Pad1)") (class "Default")
      (node (ref "C25") (pin "1") (pinfunction "1_1") (pintype "passive"))
      (node (ref "C27") (pin "2") (pinfunction "2_2") (pintype "passive"))
      (node (ref "R17") (pin "2") (pinfunction "2_2") (pintype "passive"))
      (node (ref "R18") (pin "1") (pinfunction "1_1") (pintype "passive"))
    )
    (net (code "25") (name "Net-(C25-Pad2)") (class "Default")
      (node (ref "C25") (pin "2") (pinfunction "2_2") (pintype "passive"))
      (node (ref "CONTOUR") (pin "1") (pinfunction "1_1") (pintype "passive"))
    )
    (net (code "26") (name "Net-(C26-Pad1)") (class "Default")
      (node (ref "C26") (pin "1") (pinfunction "1_1") (pintype "passive"))
      (node (ref "R18") (pin "2") (pinfunction "2_2") (pintype "passive"))
      (node (ref "R19") (pin "1") (pinfunction "1_1") (pintype "passive"))
    )
    (net (code "27") (name "Net-(C26-Pad2)") (class "Default")
      (node (ref "C26") (pin "2") (pinfunction "2_2") (pintype "passive"))
      (node (ref "CONTOUR") (pin "3") (pinfunction "3_3") (pintype "passive"))
    )
    (net (code "28") (name "Net-(C27-Pad1)") (class "Default")
      (node (ref "C27") (pin "1") (pinfunction "1_1") (pintype "passive"))
      (node (ref "C28") (pin "+") (pinfunction "+_+") (pintype "passive"))
      (node (ref "R19") (pin "2") (pinfunction "2_2") (pintype "passive"))
    )
    (net (code "29") (name "Net-(C28-Pad-)") (class "Default")
      (node (ref "C28") (pin "-") (pinfunction "-_-") (pintype "passive"))
      (node (ref "R20") (pin "1") (pinfunction "1_1") (pintype "passive"))
    )
    (net (code "30") (name "Net-(C32-Pad+)") (class "Default")
      (node (ref "C32") (pin "+") (pinfunction "+_+") (pintype "passive"))
      (node (ref "VOL") (pin "2") (pinfunction "2_2") (pintype "passive"))
    )
    (net (code "31") (name "Net-(CLIPA-1)") (class "Default")
      (node (ref "C19") (pin "2") (pinfunction "2_2") (pintype "passive"))
      (node (ref "CLIP") (pin "A1") (pinfunction "1_A1") (pintype "passive"))
      (node (ref "D3") (pin "P$1") (pinfunction "C_P$1") (pintype "passive"))
      (node (ref "D4") (pin "ANODE") (pinfunction "A_ANODE") (pintype "passive"))
    )
    (net (code "32") (name "Net-(CLIPA-3)") (class "Default")
      (node (ref "CLIP") (pin "A3") (pinfunction "3_A3") (pintype "passive"))
      (node (ref "D5") (pin "A") (pinfunction "A_A") (pintype "passive"))
      (node (ref "D6") (pin "C") (pinfunction "C_C") (pintype "passive"))
    )
    (net (code "33") (name "Net-(D3-A)") (class "Default")
      (node (ref "C19") (pin "1") (pinfunction "1_1") (pintype "passive"))
      (node (ref "C20") (pin "2") (pinfunction "2_2") (pintype "passive"))
      (node (ref "D3") (pin "ANODE") (pinfunction "A_ANODE") (pintype "passive"))
      (node (ref "D4") (pin "P$1") (pinfunction "C_P$1") (pintype "passive"))
      (node (ref "D5") (pin "C") (pinfunction "C_C") (pintype "passive"))
      (node (ref "D6") (pin "A") (pinfunction "A_A") (pintype "passive"))
      (node (ref "R12") (pin "2") (pinfunction "2_2") (pintype "passive"))
      (node (ref "R13") (pin "2") (pinfunction "2_2") (pintype "passive"))
    )
    (net (code "34") (name "Net-(HIGHA-1)") (class "Default")
      (node (ref "C30") (pin "2") (pinfunction "2_2") (pintype "passive"))
      (node (ref "HIGH") (pin "A1") (pinfunction "1_A1") (pintype "passive"))
    )
    (net (code "35") (name "Net-(HIGHA-2)") (class "Default")
      (node (ref "C29") (pin "2") (pinfunction "2_2") (pintype "passive"))
      (node (ref "HIGH") (pin "A2") (pinfunction "2_A2") (pintype "passive"))
      (node (ref "IC2") (pin "6") (pinfunction "-IN_6") (pintype "input"))
      (node (ref "R20") (pin "2") (pinfunction "2_2") (pintype "passive"))
      (node (ref "R21") (pin "1") (pinfunction "1_1") (pintype "passive"))
    )
    (net (code "36") (name "Net-(HIGHA-3)") (class "Default")
      (node (ref "C31") (pin "2") (pinfunction "2_2") (pintype "passive"))
      (node (ref "HIGH") (pin "A3") (pinfunction "3_A3") (pintype "passive"))
    )
    (net (code "37") (name "Net-(IC1A--IN)") (class "Default")
      (node (ref "C17") (pin "2") (pinfunction "2_2") (pintype "passive"))
      (node (ref "IC1") (pin "2") (pinfunction "-IN_2") (pintype "input"))
      (node (ref "R10") (pin "2") (pinfunction "2_2") (pintype "passive"))
      (node (ref "R11") (pin "1") (pinfunction "1_1") (pintype "passive"))
    )
    (net (code "38") (name "Net-(IC1A-OUT)") (class "Default")
      (node (ref "C17") (pin "1") (pinfunction "1_1") (pintype "passive"))
      (node (ref "C18") (pin "2") (pinfunction "2_2") (pintype "passive"))
      (node (ref "IC1") (pin "1") (pinfunction "OUT_1") (pintype "output"))
      (node (ref "R11") (pin "2") (pinfunction "2_2") (pintype "passive"))
    )
    (net (code "39") (name "Net-(IC1B-+IN)") (class "Default")
      (node (ref "C13") (pin "1") (pinfunction "1_1") (pintype "passive"))
      (node (ref "IC1") (pin "5") (pinfunction "+IN_5") (pintype "input"))
      (node (ref "R8") (pin "1") (pinfunction "1_1") (pintype "passive"))
    )
    (net (code "40") (name "Net-(IC1B--IN)") (class "Default")
      (node (ref "C14") (pin "2") (pinfunction "2_2") (pintype "passive"))
      (node (ref "GAIN") (pin "1") (pinfunction "1_1") (pintype "passive"))
      (node (ref "IC1") (pin "6") (pinfunction "-IN_6") (pintype "input"))
      (node (ref "R9") (pin "2") (pinfunction "2_2") (pintype "passive"))
    )
    (net (code "41") (name "Net-(IC1B-OUT)") (class "Default")
      (node (ref "C14") (pin "1") (pinfunction "1_1") (pintype "passive"))
      (node (ref "GAIN") (pin "2") (pinfunction "2_2") (pintype "passive"))
      (node (ref "IC1") (pin "7") (pinfunction "OUT_7") (pintype "output"))
    )
    (net (code "42") (name "Net-(IC2A-+IN)") (class "Default")
      (node (ref "IC2") (pin "3") (pinfunction "+IN_3") (pintype "input"))
      (node (ref "TREBLE") (pin "2") (pinfunction "2_2") (pintype "passive"))
    )
    (net (code "43") (name "Net-(IC2A--IN)") (class "Default")
      (node (ref "C23") (pin "2") (pinfunction "2_2") (pintype "passive"))
      (node (ref "IC2") (pin "2") (pinfunction "-IN_2") (pintype "input"))
      (node (ref "R15") (pin "1") (pinfunction "1_1") (pintype "passive"))
      (node (ref "R16") (pin "1") (pinfunction "1_1") (pintype "passive"))
    )
    (net (code "44") (name "Net-(IC2A-OUT)") (class "Default")
      (node (ref "C23") (pin "1") (pinfunction "1_1") (pintype "passive"))
      (node (ref "IC2") (pin "1") (pinfunction "OUT_1") (pintype "output"))
      (node (ref "R15") (pin "2") (pinfunction "2_2") (pintype "passive"))
      (node (ref "R17") (pin "1") (pinfunction "1_1") (pintype "passive"))
    )
    (net (code "45") (name "Net-(IC2B-OUT)") (class "Default")
      (node (ref "C29") (pin "1") (pinfunction "1_1") (pintype "passive"))
      (node (ref "C30") (pin "1") (pinfunction "1_1") (pintype "passive"))
      (node (ref "C31") (pin "1") (pinfunction "1_1") (pintype "passive"))
      (node (ref "IC2") (pin "7") (pinfunction "OUT_7") (pintype "output"))
      (node (ref "R21") (pin "2") (pinfunction "2_2") (pintype "passive"))
      (node (ref "VOL") (pin "3") (pinfunction "3_3") (pintype "passive"))
    )
    (net (code "46") (name "Net-(K1A-+)") (class "Default")
      (node (ref "C12") (pin "1") (pinfunction "1_1") (pintype "passive"))
      (node (ref "D2") (pin "1") (pinfunction "1_1") (pintype "passive"))
      (node (ref "K1") (pin "1") (pinfunction "+_1") (pintype "passive"))
      (node (ref "REG2") (pin "1") (pinfunction "OUTPUT_1") (pintype "power_in"))
    )
    (net (code "47") (name "Net-(K1A--)") (class "Default")
      (node (ref "D2") (pin "2") (pinfunction "2_2") (pintype "passive"))
      (node (ref "K1") (pin "8") (pinfunction "-_8") (pintype "passive"))
      (node (ref "Q1") (pin "3") (pinfunction "C_3") (pintype "passive"))
    )
    (net (code "48") (name "Net-(K1B-O)") (class "Default")
      (node (ref "K1") (pin "2") (pinfunction "O_2") (pintype "passive"))
      (node (ref "K1") (pin "7") (pinfunction "O_7") (pintype "passive"))
    )
    (net (code "49") (name "Net-(K2-A)") (class "Default")
      (node (ref "K2") (pin "1") (pinfunction "A_1") (pintype "passive"))
      (node (ref "R6") (pin "2") (pinfunction "2_2") (pintype "passive"))
    )
    (net (code "50") (name "Net-(LEDB-S)") (class "Default")
      (node (ref "BRIGHT") (pin "2") (pinfunction "2_2") (pintype "passive"))
      (node (ref "BRIGHT") (pin "3") (pinfunction "3_3") (pintype "passive"))
      (node (ref "LED") (pin "1") (pinfunction "S_1") (pintype "passive"))
    )
    (net (code "51") (name "Net-(Q1-B)") (class "Default")
      (node (ref "Q1") (pin "1") (pinfunction "B_1") (pintype "passive"))
      (node (ref "R5") (pin "2") (pinfunction "2_2") (pintype "passive"))
    )
    (net (code "52") (name "Vb") (class "Default")
      (node (ref "C24") (pin "1") (pinfunction "1_1") (pintype "passive"))
      (node (ref "C3") (pin "+") (pinfunction "+_+") (pintype "passive"))
      (node (ref "CLIP") (pin "A2") (pinfunction "2_A2") (pintype "passive"))
      (node (ref "CONTOUR") (pin "2") (pinfunction "2_2") (pintype "passive"))
      (node (ref "IC1") (pin "3") (pinfunction "+IN_3") (pintype "input"))
      (node (ref "IC2") (pin "5") (pinfunction "+IN_5") (pintype "input"))
      (node (ref "R14") (pin "1") (pinfunction "1_1") (pintype "passive"))
      (node (ref "R2") (pin "2") (pinfunction "2_2") (pintype "passive"))
      (node (ref "R3") (pin "2") (pinfunction "2_2") (pintype "passive"))
      (node (ref "R8") (pin "2") (pinfunction "2_2") (pintype "passive"))
      (node (ref "VOL") (pin "1") (pinfunction "1_1") (pintype "passive"))
    )
    (net (code "53") (name "Vr") (class "Default")
      (node (ref "C2") (pin "+") (pinfunction "+_+") (pintype "passive"))
      (node (ref "C4") (pin "1") (pinfunction "1_1") (pintype "passive"))
      (node (ref "C5") (pin "1") (pinfunction "1_1") (pintype "passive"))
      (node (ref "IC1") (pin "8") (pinfunction "V+_8") (pintype "power_in"))
      (node (ref "IC2") (pin "8") (pinfunction "V+_8") (pintype "power_in"))
      (node (ref "R1") (pin "2") (pinfunction "2_2") (pintype "passive"))
      (node (ref "R2") (pin "1") (pinfunction "1_1") (pintype "passive"))
    )
    (net (code "54") (name "unconnected-(INPUT-PadR)") (class "Default")
      (node (ref "INPUT") (pin "R") (pinfunction "R_R") (pintype "passive+no_connect"))
    )
    (net (code "55") (name "unconnected-(OUTPUT-PadR)") (class "Default")
      (node (ref "OUTPUT") (pin "R") (pinfunction "R_R") (pintype "passive+no_connect"))
    )
  )
)
